# IO_Expander.net
KiCad netlist of a schematic drawn in Altium Designer
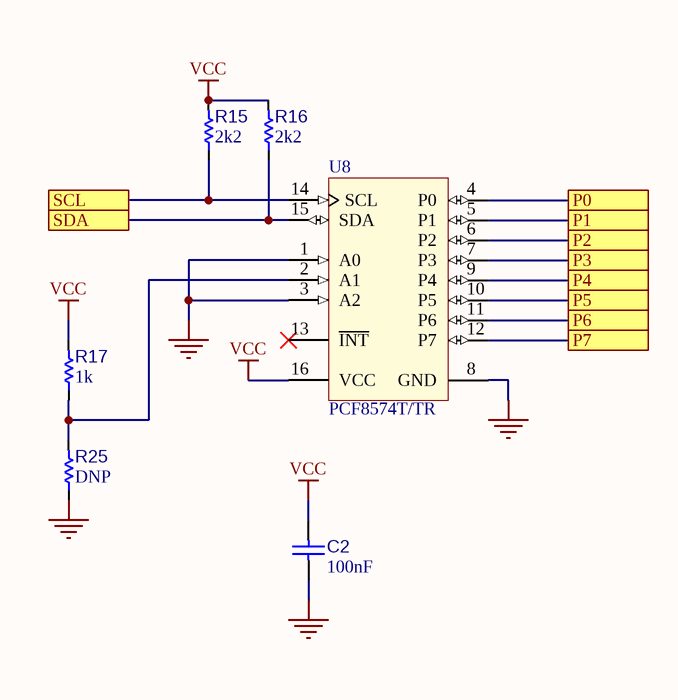
[diagram p0: IO Expander.SchDoc]

(export (version "E")
  (design (tool "Eeschema 10.0.6"))
  (components
    (comp (ref "C2")
      (value "100nF")
      (footprint "C_1608[0603]")
      (description "Capacitor type 1")
      (fields (field (name "TOLERANCE") "10%") (field (name "Comment") "CAP CER 100nF 50V 0603"))
      (libsource (lib "TEP_243-Altium_DBLib") (part "capacitor"))
    )
    (comp (ref "R15")
      (value "2k2")
      (footprint "R_1005[0402]")
      (description "Resistor type 1")
      (fields (field (name "TOLERANCE") "1%") (field (name "Comment") "Res 2k2 1% 0402"))
      (libsource (lib "TEP_243-Altium_DBLib") (part "resistor"))
    )
    (comp (ref "R16")
      (value "2k2")
      (footprint "R_1005[0402]")
      (description "Resistor type 1")
      (fields (field (name "TOLERANCE") "1%") (field (name "Comment") "Res 2k2 1% 0402"))
      (libsource (lib "TEP_243-Altium_DBLib") (part "resistor"))
    )
    (comp (ref "R17")
      (value "1k")
      (footprint "R_1608[0603]")
      (description "Resistor type 1")
      (fields (field (name "TOLERANCE") "1%") (field (name "Comment") "Res 1k 1% 0603"))
      (libsource (lib "TEP_243-Altium_DBLib") (part "resistor"))
    )
    (comp (ref "R25")
      (value "DNP")
      (footprint "R_1608[0603]")
      (description "Resistor type 1")
      (fields (field (name "TOLERANCE") "1%") (field (name "Comment") "Res 1k 1% 0603"))
      (libsource (lib "TEP_243-Altium_DBLib") (part "resistor"))
    )
    (comp (ref "U8")
      (value "PCF8574T/TR")
      (footprint "SOIC127P1030X265-16N")
      (description "Remote 8-bit I/O expander for I2C-bus")
      (libsource (lib "TEP-AltiumLib-ICs") (part "U_PCF8574-SOIC"))
    )
  )
  (nets
    (net (code "1") (name "/P0") (class "Default")
      (node (ref "U8") (pin "4") (pinfunction "P0_4") (pintype "bidirectional"))
    )
    (net (code "2") (name "/P1") (class "Default")
      (node (ref "U8") (pin "5") (pinfunction "P1_5") (pintype "bidirectional"))
    )
    (net (code "3") (name "/P2") (class "Default")
      (node (ref "U8") (pin "6") (pinfunction "P2_6") (pintype "bidirectional"))
    )
    (net (code "4") (name "/P3") (class "Default")
      (node (ref "U8") (pin "7") (pinfunction "P3_7") (pintype "bidirectional"))
    )
    (net (code "5") (name "/P4") (class "Default")
      (node (ref "U8") (pin "9") (pinfunction "P4_9") (pintype "bidirectional"))
    )
    (net (code "6") (name "/P5") (class "Default")
      (node (ref "U8") (pin "10") (pinfunction "P5_10") (pintype "bidirectional"))
    )
    (net (code "7") (name "/P6") (class "Default")
      (node (ref "U8") (pin "11") (pinfunction "P6_11") (pintype "bidirectional"))
    )
    (net (code "8") (name "/P7") (class "Default")
      (node (ref "U8") (pin "12") (pinfunction "P7_12") (pintype "bidirectional"))
    )
    (net (code "9") (name "/SCL") (class "Default")
      (node (ref "R15") (pin "1") (pinfunction "1_1") (pintype "passive"))
      (node (ref "U8") (pin "14") (pinfunction "SCL_14") (pintype "input"))
    )
    (net (code "10") (name "/SDA") (class "Default")
      (node (ref "R16") (pin "1") (pinfunction "1_1") (pintype "passive"))
      (node (ref "U8") (pin "15") (pinfunction "SDA_15") (pintype "bidirectional"))
    )
    (net (code "11") (name "GND") (class "Default")
      (node (ref "C2") (pin "1") (pinfunction "1_1") (pintype "passive"))
      (node (ref "R25") (pin "1") (pinfunction "1_1") (pintype "passive"))
      (node (ref "U8") (pin "1") (pinfunction "A0_1") (pintype "input"))
      (node (ref "U8") (pin "3") (pinfunction "A2_3") (pintype "input"))
      (node (ref "U8") (pin "8") (pinfunction "GND_8") (pintype "power_in"))
    )
    (net (code "12") (name "Net-(U8-A1)") (class "Default")
      (node (ref "R17") (pin "1") (pinfunction "1_1") (pintype "passive"))
      (node (ref "R25") (pin "2") (pinfunction "2_2") (pintype "passive"))
      (node (ref "U8") (pin "2") (pinfunction "A1_2") (pintype "input"))
    )
    (net (code "13") (name "VCC") (class "Default")
      (node (ref "C2") (pin "2") (pinfunction "2_2") (pintype "passive"))
      (node (ref "R15") (pin "2") (pinfunction "2_2") (pintype "passive"))
      (node (ref "R16") (pin "2") (pinfunction "2_2") (pintype "passive"))
      (node (ref "R17") (pin "2") (pinfunction "2_2") (pintype "passive"))
      (node (ref "U8") (pin "16") (pinfunction "VCC_16") (pintype "power_in"))
    )
    (net (code "14") (name "unconnected-(U8-~{INT}-Pad13)") (class "Default")
      (node (ref "U8") (pin "13") (pinfunction "~{INT}_13") (pintype "open_collector+no_connect"))
    )
  )
)
